# SEQUIN_TEAR.net
KiCad netlist of a schematic drawn in EAGLE
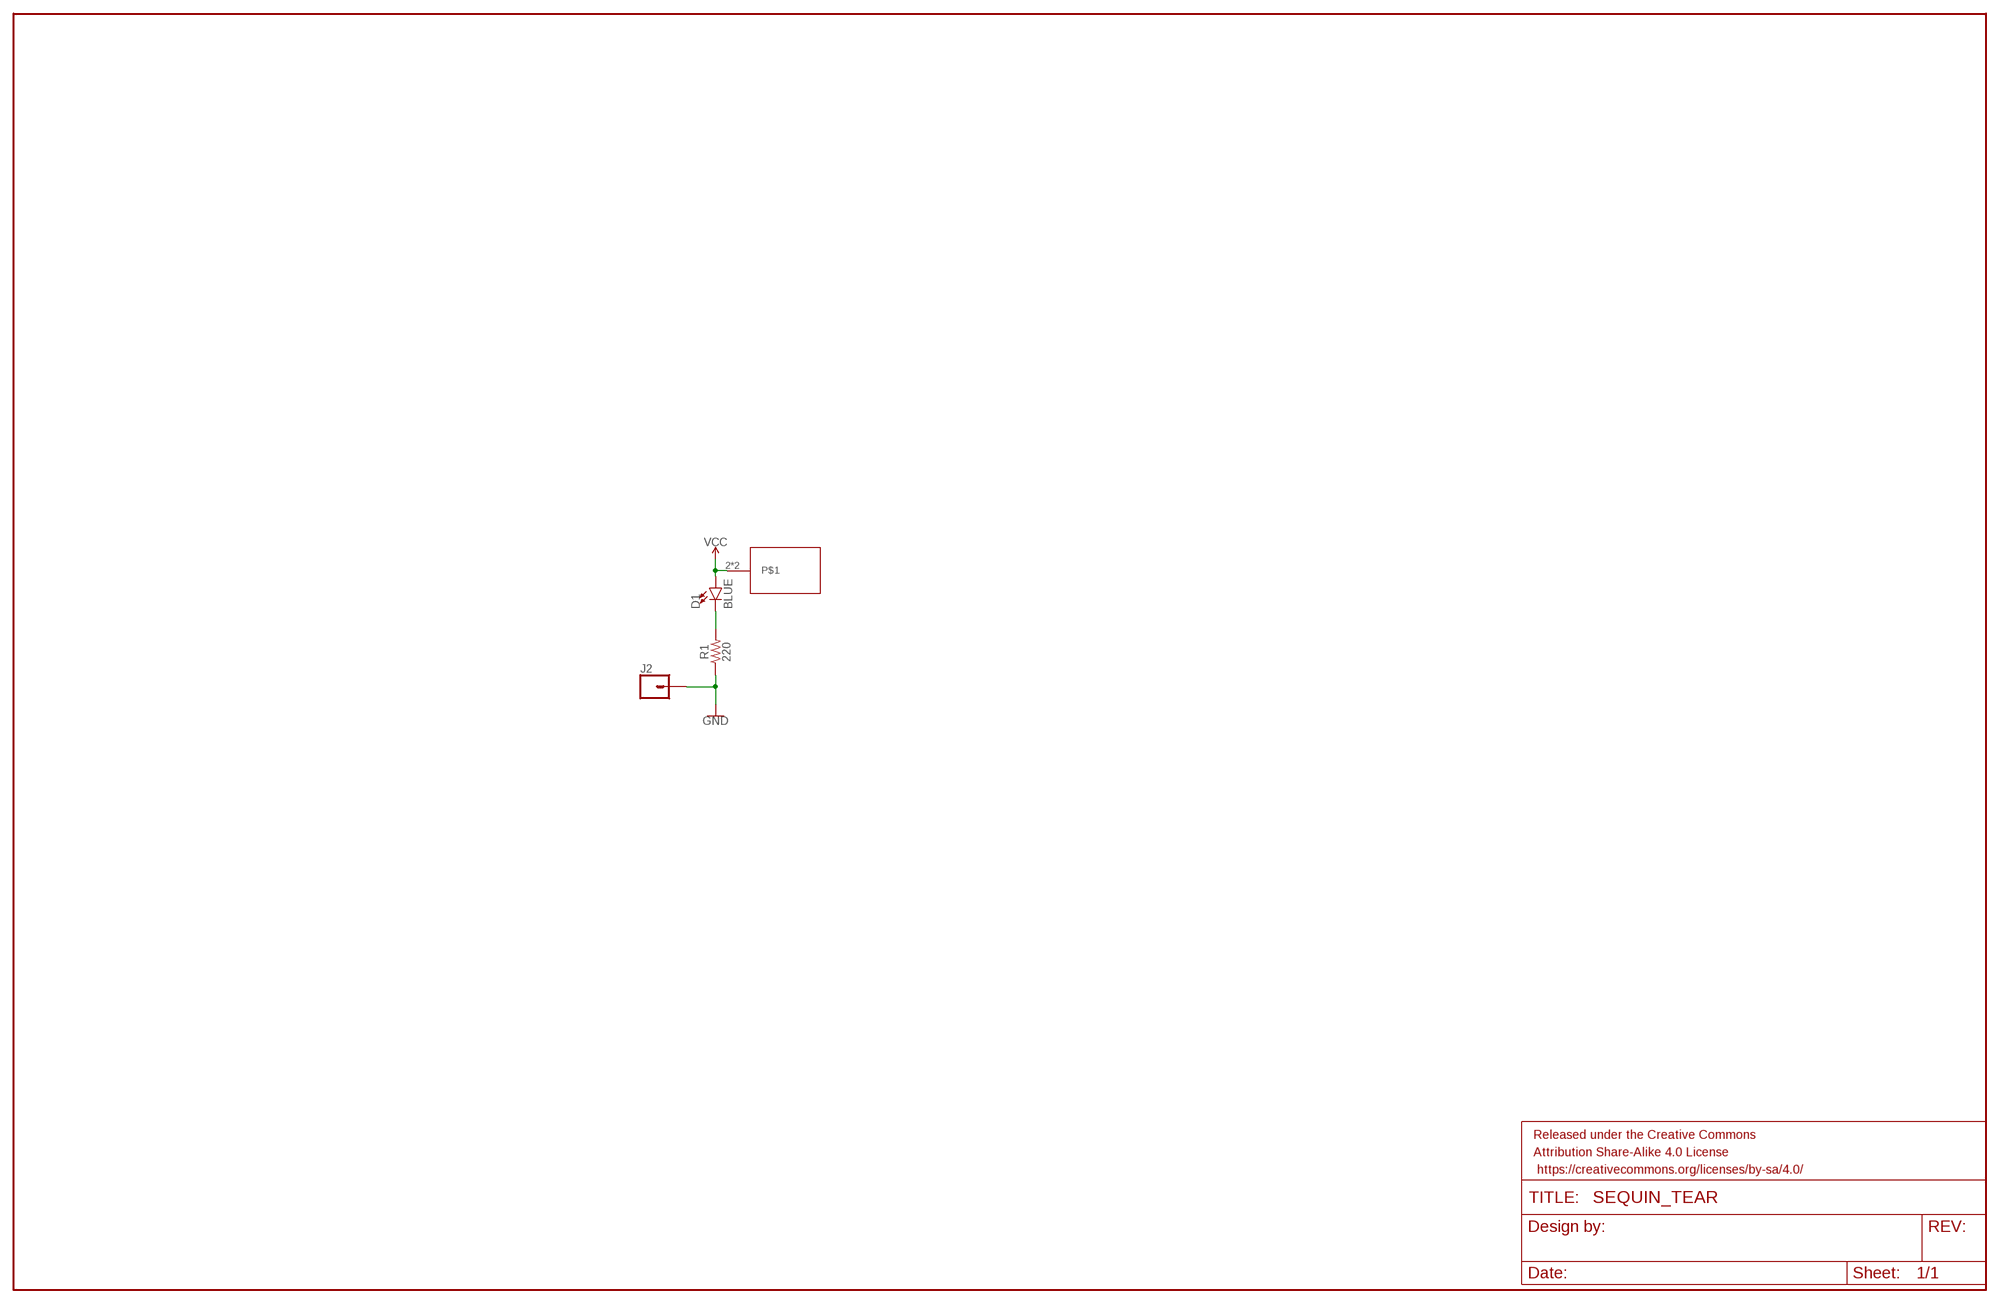
[diagram p0: schematic, sheet 1]

(export (version "E")
  (design (tool "Eeschema 10.0.6"))
  (components
    (comp (ref "D1")
      (value "BLUE")
      (footprint "eagle-import:LED-1206")
      (libsource (lib "eagle-import") (part "LED-BLUE1206"))
    )
    (comp (ref "FRAME1")
      (value "FRAME-LEDGER")
      (footprint "eagle-import:CREATIVE_COMMONS")
      (libsource (lib "eagle-import") (part "FRAME-LEDGER"))
    )
    (comp (ref "J2")
      (value "CONN_01SPRING-CONN")
      (footprint "eagle-import:SPRING-CONNECTOR")
      (libsource (lib "eagle-import") (part "CONN_01SPRING-CONN"))
    )
    (comp (ref "R1")
      (value "220")
      (footprint "eagle-import:0603")
      (libsource (lib "eagle-import") (part "220OHM-0603-1/10W-1%"))
    )
    (comp (ref "U$1")
      (value "TEARDROP")
      (footprint "eagle-import:TEARDROP")
      (libsource (lib "eagle-import") (part "TEARDROP"))
    )
  )
  (nets
    (net (code "1") (name "GND") (class "Default")
      (node (ref "J2") (pin "P$2") (pinfunction "1_P$2") (pintype "passive"))
      (node (ref "R1") (pin "1") (pinfunction "1_1") (pintype "passive"))
    )
    (net (code "2") (name "Net-(D1-PadC)") (class "Default")
      (node (ref "D1") (pin "C") (pinfunction "C_C") (pintype "passive"))
      (node (ref "R1") (pin "2") (pinfunction "2_2") (pintype "passive"))
    )
    (net (code "3") (name "VCC") (class "Default")
      (node (ref "D1") (pin "A") (pinfunction "A_A") (pintype "passive"))
      (node (ref "U$1") (pin "2") (pinfunction "P$1_2") (pintype "bidirectional"))
      (node (ref "U$1") (pin "VCC") (pinfunction "P$1_VCC") (pintype "bidirectional"))
    )
  )
)
